# FD1.net
KiCad netlist of a schematic drawn in EAGLE
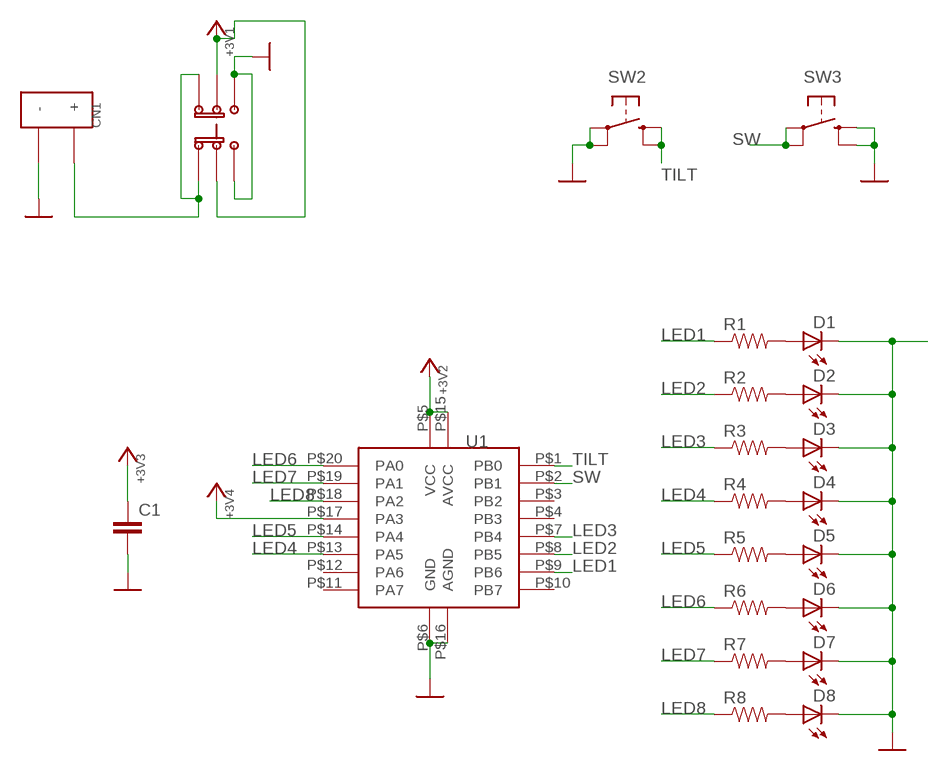
[diagram p0: schematic, sheet 1]

(export (version "E")
  (design (tool "Eeschema 10.0.6"))
  (components
    (comp (ref "C1")
      (value "CAPTH_5MML")
      (footprint "eagle-import:CAP_TH_5MM_L")
      (libsource (lib "eagle-import") (part "CAPTH_5MML"))
    )
    (comp (ref "CN1")
      (value "BAT_UM3X2")
      (footprint "eagle-import:BAT_UM3X2")
      (libsource (lib "eagle-import") (part "BAT_UM3X2"))
    )
    (comp (ref "D1")
      (value "LED5MM")
      (footprint "eagle-import:SPARKFUN_LED5MM")
      (libsource (lib "eagle-import") (part "LED5MM"))
    )
    (comp (ref "D2")
      (value "LED5MM")
      (footprint "eagle-import:SPARKFUN_LED5MM")
      (libsource (lib "eagle-import") (part "LED5MM"))
    )
    (comp (ref "D3")
      (value "LED5MM")
      (footprint "eagle-import:SPARKFUN_LED5MM")
      (libsource (lib "eagle-import") (part "LED5MM"))
    )
    (comp (ref "D4")
      (value "LED5MM")
      (footprint "eagle-import:SPARKFUN_LED5MM")
      (libsource (lib "eagle-import") (part "LED5MM"))
    )
    (comp (ref "D5")
      (value "LED5MM")
      (footprint "eagle-import:SPARKFUN_LED5MM")
      (libsource (lib "eagle-import") (part "LED5MM"))
    )
    (comp (ref "D6")
      (value "LED5MM")
      (footprint "eagle-import:SPARKFUN_LED5MM")
      (libsource (lib "eagle-import") (part "LED5MM"))
    )
    (comp (ref "D7")
      (value "LED5MM")
      (footprint "eagle-import:SPARKFUN_LED5MM")
      (libsource (lib "eagle-import") (part "LED5MM"))
    )
    (comp (ref "D8")
      (value "LED5MM")
      (footprint "eagle-import:SPARKFUN_LED5MM")
      (libsource (lib "eagle-import") (part "LED5MM"))
    )
    (comp (ref "R1")
      (value "RESTH_10MML")
      (footprint "eagle-import:R_TH_10MM_L")
      (libsource (lib "eagle-import") (part "RESTH_10MML"))
    )
    (comp (ref "R2")
      (value "RESTH_10MML")
      (footprint "eagle-import:R_TH_10MM_L")
      (libsource (lib "eagle-import") (part "RESTH_10MML"))
    )
    (comp (ref "R3")
      (value "RESTH_10MML")
      (footprint "eagle-import:R_TH_10MM_L")
      (libsource (lib "eagle-import") (part "RESTH_10MML"))
    )
    (comp (ref "R4")
      (value "RESTH_10MML")
      (footprint "eagle-import:R_TH_10MM_L")
      (libsource (lib "eagle-import") (part "RESTH_10MML"))
    )
    (comp (ref "R5")
      (value "RESTH_10MML")
      (footprint "eagle-import:R_TH_10MM_L")
      (libsource (lib "eagle-import") (part "RESTH_10MML"))
    )
    (comp (ref "R6")
      (value "RESTH_10MML")
      (footprint "eagle-import:R_TH_10MM_L")
      (libsource (lib "eagle-import") (part "RESTH_10MML"))
    )
    (comp (ref "R7")
      (value "RESTH_10MML")
      (footprint "eagle-import:R_TH_10MM_L")
      (libsource (lib "eagle-import") (part "RESTH_10MML"))
    )
    (comp (ref "R8")
      (value "RESTH_10MML")
      (footprint "eagle-import:R_TH_10MM_L")
      (libsource (lib "eagle-import") (part "RESTH_10MML"))
    )
    (comp (ref "SW2")
      (value "SW_TACTRBS04021-G")
      (footprint "eagle-import:SW_RBS040210-G")
      (libsource (lib "eagle-import") (part "SW_TACTRBS04021-G"))
    )
    (comp (ref "SW3")
      (value "SW_TACTTH_L")
      (footprint "eagle-import:SW_TACT_L")
      (libsource (lib "eagle-import") (part "SW_TACTTH_L"))
    )
    (comp (ref "SW4")
      (value "SW_IS-1250IS2235")
      (footprint "eagle-import:SW_IS2235")
      (libsource (lib "eagle-import") (part "SW_IS-1250IS2235"))
    )
    (comp (ref "U1")
      (value "MCU_ATTINY861PU")
      (footprint "eagle-import:DIP20")
      (libsource (lib "eagle-import") (part "MCU_ATTINY861PU"))
    )
  )
  (nets
    (net (code "1") (name "/LED1") (class "Default")
      (node (ref "R1") (pin "1") (pinfunction "1_1") (pintype "passive"))
      (node (ref "U1") (pin "P$9") (pinfunction "PB6_P$9") (pintype "bidirectional"))
    )
    (net (code "2") (name "/LED2") (class "Default")
      (node (ref "R2") (pin "1") (pinfunction "1_1") (pintype "passive"))
      (node (ref "U1") (pin "P$8") (pinfunction "PB5_P$8") (pintype "bidirectional"))
    )
    (net (code "3") (name "/LED3") (class "Default")
      (node (ref "R3") (pin "1") (pinfunction "1_1") (pintype "passive"))
      (node (ref "U1") (pin "P$7") (pinfunction "PB4_P$7") (pintype "bidirectional"))
    )
    (net (code "4") (name "/LED4") (class "Default")
      (node (ref "R4") (pin "1") (pinfunction "1_1") (pintype "passive"))
      (node (ref "U1") (pin "P$13") (pinfunction "PA5_P$13") (pintype "bidirectional"))
    )
    (net (code "5") (name "/LED5") (class "Default")
      (node (ref "R5") (pin "1") (pinfunction "1_1") (pintype "passive"))
      (node (ref "U1") (pin "P$14") (pinfunction "PA4_P$14") (pintype "bidirectional"))
    )
    (net (code "6") (name "/LED6") (class "Default")
      (node (ref "R6") (pin "1") (pinfunction "1_1") (pintype "passive"))
      (node (ref "U1") (pin "P$20") (pinfunction "PA0_P$20") (pintype "bidirectional"))
    )
    (net (code "7") (name "/LED7") (class "Default")
      (node (ref "R7") (pin "1") (pinfunction "1_1") (pintype "passive"))
      (node (ref "U1") (pin "P$19") (pinfunction "PA1_P$19") (pintype "bidirectional"))
    )
    (net (code "8") (name "/LED8") (class "Default")
      (node (ref "R8") (pin "1") (pinfunction "1_1") (pintype "passive"))
      (node (ref "U1") (pin "P$18") (pinfunction "PA2_P$18") (pintype "bidirectional"))
    )
    (net (code "9") (name "/SW") (class "Default")
      (node (ref "SW3") (pin "P$1") (pinfunction "P_P$1") (pintype "passive"))
      (node (ref "SW3") (pin "P$2") (pinfunction "P1_P$2") (pintype "passive"))
      (node (ref "U1") (pin "P$2") (pinfunction "PB1_P$2") (pintype "bidirectional"))
    )
    (net (code "10") (name "/TILT") (class "Default")
      (node (ref "SW2") (pin "P$3") (pinfunction "S_P$3") (pintype "passive"))
      (node (ref "SW2") (pin "P$4") (pinfunction "S1_P$4") (pintype "passive"))
      (node (ref "U1") (pin "P$1") (pinfunction "PB0_P$1") (pintype "bidirectional"))
    )
    (net (code "11") (name "Net-(CN1-+)") (class "Default")
      (node (ref "CN1") (pin "P$P") (pinfunction "+_P$P") (pintype "power_in"))
      (node (ref "SW4") (pin "P$A1") (pinfunction "P$A1_P$A1") (pintype "bidirectional"))
      (node (ref "SW4") (pin "P$A2") (pinfunction "P$A2_P$A2") (pintype "bidirectional"))
    )
    (net (code "12") (name "Net-(D1-PadA)") (class "Default")
      (node (ref "D1") (pin "A") (pinfunction "A_A") (pintype "passive"))
      (node (ref "R1") (pin "2") (pinfunction "2_2") (pintype "passive"))
    )
    (net (code "13") (name "Net-(D2-PadA)") (class "Default")
      (node (ref "D2") (pin "A") (pinfunction "A_A") (pintype "passive"))
      (node (ref "R2") (pin "2") (pinfunction "2_2") (pintype "passive"))
    )
    (net (code "14") (name "Net-(D3-PadA)") (class "Default")
      (node (ref "D3") (pin "A") (pinfunction "A_A") (pintype "passive"))
      (node (ref "R3") (pin "2") (pinfunction "2_2") (pintype "passive"))
    )
    (net (code "15") (name "Net-(D4-PadA)") (class "Default")
      (node (ref "D4") (pin "A") (pinfunction "A_A") (pintype "passive"))
      (node (ref "R4") (pin "2") (pinfunction "2_2") (pintype "passive"))
    )
    (net (code "16") (name "Net-(D5-PadA)") (class "Default")
      (node (ref "D5") (pin "A") (pinfunction "A_A") (pintype "passive"))
      (node (ref "R5") (pin "2") (pinfunction "2_2") (pintype "passive"))
    )
    (net (code "17") (name "Net-(D6-PadA)") (class "Default")
      (node (ref "D6") (pin "A") (pinfunction "A_A") (pintype "passive"))
      (node (ref "R6") (pin "2") (pinfunction "2_2") (pintype "passive"))
    )
    (net (code "18") (name "Net-(D7-PadA)") (class "Default")
      (node (ref "D7") (pin "A") (pinfunction "A_A") (pintype "passive"))
      (node (ref "R7") (pin "2") (pinfunction "2_2") (pintype "passive"))
    )
    (net (code "19") (name "Net-(D8-PadA)") (class "Default")
      (node (ref "D8") (pin "A") (pinfunction "A_A") (pintype "passive"))
      (node (ref "R8") (pin "2") (pinfunction "2_2") (pintype "passive"))
    )
    (net (code "20") (name "POW_+3V3") (class "Default")
      (node (ref "C1") (pin "1") (pinfunction "1_1") (pintype "passive"))
      (node (ref "SW4") (pin "P$C1") (pinfunction "P$C1_P$C1") (pintype "bidirectional"))
      (node (ref "SW4") (pin "P$C2") (pinfunction "P$C2_P$C2") (pintype "bidirectional"))
      (node (ref "U1") (pin "P$15") (pinfunction "AVCC_P$15") (pintype "bidirectional"))
      (node (ref "U1") (pin "P$17") (pinfunction "PA3_P$17") (pintype "bidirectional"))
      (node (ref "U1") (pin "P$5") (pinfunction "VCC_P$5") (pintype "bidirectional"))
    )
    (net (code "21") (name "POW_GND") (class "Default")
      (node (ref "C1") (pin "2") (pinfunction "2_2") (pintype "passive"))
      (node (ref "CN1") (pin "P$M") (pinfunction "-_P$M") (pintype "power_in"))
      (node (ref "D1") (pin "K") (pinfunction "C_K") (pintype "passive"))
      (node (ref "D2") (pin "K") (pinfunction "C_K") (pintype "passive"))
      (node (ref "D3") (pin "K") (pinfunction "C_K") (pintype "passive"))
      (node (ref "D4") (pin "K") (pinfunction "C_K") (pintype "passive"))
      (node (ref "D5") (pin "K") (pinfunction "C_K") (pintype "passive"))
      (node (ref "D6") (pin "K") (pinfunction "C_K") (pintype "passive"))
      (node (ref "D7") (pin "K") (pinfunction "C_K") (pintype "passive"))
      (node (ref "D8") (pin "K") (pinfunction "C_K") (pintype "passive"))
      (node (ref "SW2") (pin "P$1") (pinfunction "P_P$1") (pintype "passive"))
      (node (ref "SW2") (pin "P$2") (pinfunction "P1_P$2") (pintype "passive"))
      (node (ref "SW3") (pin "P$3") (pinfunction "S_P$3") (pintype "passive"))
      (node (ref "SW3") (pin "P$4") (pinfunction "S1_P$4") (pintype "passive"))
      (node (ref "SW4") (pin "P$B1") (pinfunction "P$B1_P$B1") (pintype "bidirectional"))
      (node (ref "SW4") (pin "P$B2") (pinfunction "P$B2_P$B2") (pintype "bidirectional"))
      (node (ref "U1") (pin "P$16") (pinfunction "AGND_P$16") (pintype "bidirectional"))
      (node (ref "U1") (pin "P$6") (pinfunction "GND_P$6") (pintype "bidirectional"))
    )
    (net (code "22") (name "unconnected-(U1-PA6-PadP$12)") (class "Default")
      (node (ref "U1") (pin "P$12") (pinfunction "PA6_P$12") (pintype "bidirectional"))
    )
    (net (code "23") (name "unconnected-(U1-PA7-PadP$11)") (class "Default")
      (node (ref "U1") (pin "P$11") (pinfunction "PA7_P$11") (pintype "bidirectional"))
    )
    (net (code "24") (name "unconnected-(U1-PB2-PadP$3)") (class "Default")
      (node (ref "U1") (pin "P$3") (pinfunction "PB2_P$3") (pintype "bidirectional"))
    )
    (net (code "25") (name "unconnected-(U1-PB3-PadP$4)") (class "Default")
      (node (ref "U1") (pin "P$4") (pinfunction "PB3_P$4") (pintype "bidirectional"))
    )
    (net (code "26") (name "unconnected-(U1-PB7-PadP$10)") (class "Default")
      (node (ref "U1") (pin "P$10") (pinfunction "PB7_P$10") (pintype "bidirectional"))
    )
  )
)
